# nano_neu5.net
KiCad netlist of a schematic drawn in EAGLE
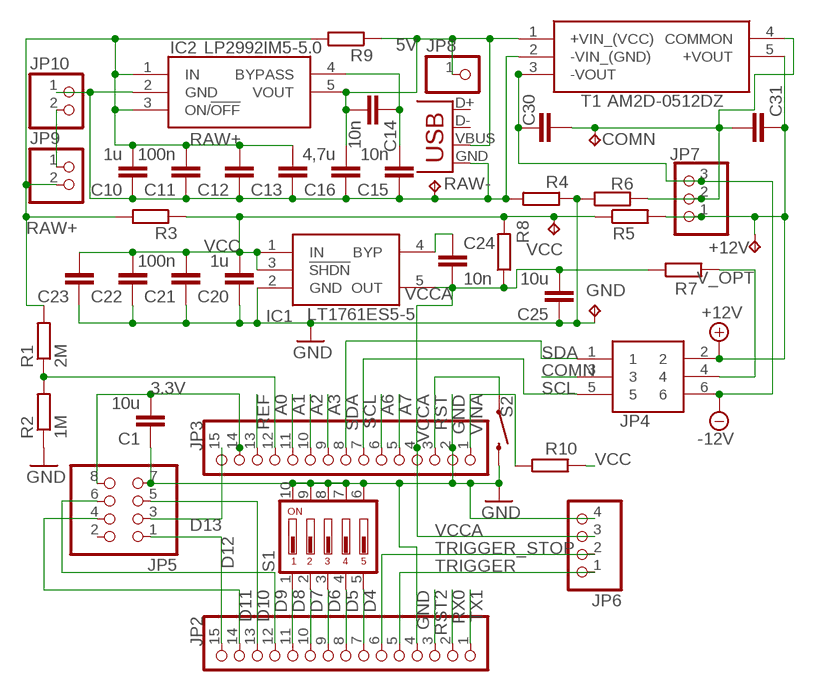
[diagram p0: schematic, sheet 1]

(export (version "E")
  (design (tool "Eeschema 10.0.6"))
  (components
    (comp (ref "+12V")
      (value "TESTPAD_TPTP09SQ")
      (footprint "eagle-import:TESTPAD_TP09SQ")
      (libsource (lib "eagle-import") (part "TESTPAD_TPTP09SQ"))
    )
    (comp (ref "C1")
      (value "10u")
      (footprint "eagle-import:RCL_C0805K")
      (libsource (lib "eagle-import") (part "RCL_C-EUC0805K"))
    )
    (comp (ref "C10")
      (value "1u")
      (footprint "eagle-import:RCL_C0805K")
      (libsource (lib "eagle-import") (part "RCL_C-EUC0805K"))
    )
    (comp (ref "C11")
      (value "100n")
      (footprint "eagle-import:RCL_C0805K")
      (libsource (lib "eagle-import") (part "RCL_C-EUC0805K"))
    )
    (comp (ref "C12")
      (value "RCL_C-EUC1206K")
      (footprint "eagle-import:RCL_C1206K")
      (libsource (lib "eagle-import") (part "RCL_C-EUC1206K"))
    )
    (comp (ref "C13")
      (value "RCL_C-EUC1206K")
      (footprint "eagle-import:RCL_C1206K")
      (libsource (lib "eagle-import") (part "RCL_C-EUC1206K"))
    )
    (comp (ref "C14")
      (value "10n")
      (footprint "eagle-import:RCL_C0805K")
      (libsource (lib "eagle-import") (part "RCL_C-EUC0805K"))
    )
    (comp (ref "C15")
      (value "10n")
      (footprint "eagle-import:RCL_C0805K")
      (libsource (lib "eagle-import") (part "RCL_C-EUC0805K"))
    )
    (comp (ref "C16")
      (value "4,7u")
      (footprint "eagle-import:RCL_C0805K")
      (libsource (lib "eagle-import") (part "RCL_C-EUC0805K"))
    )
    (comp (ref "C20")
      (value "1u")
      (footprint "eagle-import:RCL_C0805K")
      (libsource (lib "eagle-import") (part "RCL_C-EUC0805K"))
    )
    (comp (ref "C21")
      (value "100n")
      (footprint "eagle-import:RCL_C0805K")
      (libsource (lib "eagle-import") (part "RCL_C-EUC0805K"))
    )
    (comp (ref "C22")
      (value "RCL_C-EUC1206K")
      (footprint "eagle-import:RCL_C1206K")
      (libsource (lib "eagle-import") (part "RCL_C-EUC1206K"))
    )
    (comp (ref "C23")
      (value "RCL_C-EUC1206K")
      (footprint "eagle-import:RCL_C1206K")
      (libsource (lib "eagle-import") (part "RCL_C-EUC1206K"))
    )
    (comp (ref "C24")
      (value "10n")
      (footprint "eagle-import:RCL_C0805K")
      (libsource (lib "eagle-import") (part "RCL_C-EUC0805K"))
    )
    (comp (ref "C25")
      (value "10u")
      (footprint "eagle-import:RCL_C0805K")
      (libsource (lib "eagle-import") (part "RCL_C-EUC0805K"))
    )
    (comp (ref "C30")
      (value "RCL_C-EUC1206K")
      (footprint "eagle-import:RCL_C1206K")
      (libsource (lib "eagle-import") (part "RCL_C-EUC1206K"))
    )
    (comp (ref "C31")
      (value "RCL_C-EUC1206K")
      (footprint "eagle-import:RCL_C1206K")
      (libsource (lib "eagle-import") (part "RCL_C-EUC1206K"))
    )
    (comp (ref "COMN")
      (value "TESTPAD_TPTP09SQ")
      (footprint "eagle-import:TESTPAD_TP09SQ")
      (libsource (lib "eagle-import") (part "TESTPAD_TPTP09SQ"))
    )
    (comp (ref "GND")
      (value "TESTPAD_TPTP09SQ")
      (footprint "eagle-import:TESTPAD_TP09SQ")
      (libsource (lib "eagle-import") (part "TESTPAD_TPTP09SQ"))
    )
    (comp (ref "IC1")
      (value "LT1761ES5-5")
      (footprint "eagle-import:SAMACSYS_PARTS_SOT95P280X100-5N")
      (fields
        (field (name "MANUFACTURER_PART_NUMBER") "LT1761ES5-3.3#TRMPBF")
        (field (name "MOUSER_PART_NUMBER") "584-1761ES5-3.3TMPF")
      )
      (libsource (lib "eagle-import") (part "SAMACSYS_PARTS_LT1761ES5-5#TRMPBF"))
    )
    (comp (ref "IC2")
      (value "LP2992IM5-5.0")
      (footprint "eagle-import:SAMACSYS_PARTS_SOT95P280X145-5N")
      (fields
        (field (name "MANUFACTURER_PART_NUMBER") "LP2992IM5-5.0/NOPB")
        (field (name "MOUSER_PART_NUMBER") "926-2992IM5-5.0/NOPB")
      )
      (libsource (lib "eagle-import") (part "SAMACSYS_PARTS_LP2992IM5-5.0_NOPB"))
    )
    (comp (ref "JP2")
      (value "ADAFRUIT_PINHD-1X15-CB")
      (footprint "eagle-import:ADAFRUIT_1X15-CB")
      (libsource (lib "eagle-import") (part "ADAFRUIT_PINHD-1X15-CB"))
    )
    (comp (ref "JP3")
      (value "ADAFRUIT_PINHD-1X15-CB")
      (footprint "eagle-import:ADAFRUIT_1X15-CB")
      (libsource (lib "eagle-import") (part "ADAFRUIT_PINHD-1X15-CB"))
    )
    (comp (ref "JP4")
      (value "SAMACSYS_PARTS_FTSH-103-01-F-D")
      (footprint "eagle-import:SAMACSYS_PARTS_FTSH10301FD")
      (fields
        (field (name "MANUFACTURER_PART_NUMBER") "FTSH-103-01-F-D")
        (field (name "MOUSER_PART_NUMBER") "200-FTSH10301FD")
      )
      (libsource (lib "eagle-import") (part "SAMACSYS_PARTS_FTSH-103-01-F-D"))
    )
    (comp (ref "JP5")
      (value "PINHEAD_PINHD-2X4")
      (footprint "eagle-import:PINHEAD_2X04")
      (libsource (lib "eagle-import") (part "PINHEAD_PINHD-2X4"))
    )
    (comp (ref "JP6")
      (value "PINHD-1X4-CB")
      (footprint "eagle-import:ADAFRUIT_1X04-CLEANBIG")
      (libsource (lib "eagle-import") (part "PINHD-1X4-CB"))
    )
    (comp (ref "JP7")
      (value "ADAFRUIT_PINHD-1X3CB")
      (footprint "eagle-import:ADAFRUIT_1X03-CLEANBIG")
      (libsource (lib "eagle-import") (part "ADAFRUIT_PINHD-1X3CB"))
    )
    (comp (ref "JP8")
      (value "PINHEAD_PINHD-1X1")
      (footprint "eagle-import:PINHEAD_1X01")
      (libsource (lib "eagle-import") (part "PINHEAD_PINHD-1X1"))
    )
    (comp (ref "JP9")
      (value "PINHEAD_PINHD-1X2")
      (footprint "eagle-import:PINHEAD_1X02")
      (libsource (lib "eagle-import") (part "PINHEAD_PINHD-1X2"))
    )
    (comp (ref "JP10")
      (value "PINHEAD_PINHD-1X2")
      (footprint "eagle-import:PINHEAD_1X02")
      (libsource (lib "eagle-import") (part "PINHEAD_PINHD-1X2"))
    )
    (comp (ref "R1")
      (value "2M")
      (footprint "eagle-import:RCL_R0805")
      (libsource (lib "eagle-import") (part "RCL_R-EU_R0805"))
    )
    (comp (ref "R2")
      (value "1M")
      (footprint "eagle-import:RCL_R0805")
      (libsource (lib "eagle-import") (part "RCL_R-EU_R0805"))
    )
    (comp (ref "R3")
      (value "RCL_R-EU_R0805")
      (footprint "eagle-import:RCL_R0805")
      (libsource (lib "eagle-import") (part "RCL_R-EU_R0805"))
    )
    (comp (ref "R4")
      (value "RCL_R-EU_R0805")
      (footprint "eagle-import:RCL_R0805")
      (libsource (lib "eagle-import") (part "RCL_R-EU_R0805"))
    )
    (comp (ref "R5")
      (value "RCL_R-EU_R0805")
      (footprint "eagle-import:RCL_R0805")
      (libsource (lib "eagle-import") (part "RCL_R-EU_R0805"))
    )
    (comp (ref "R6")
      (value "RCL_R-EU_R0805")
      (footprint "eagle-import:RCL_R0805")
      (libsource (lib "eagle-import") (part "RCL_R-EU_R0805"))
    )
    (comp (ref "R7")
      (value "RCL_R-EU_R0805")
      (footprint "eagle-import:RCL_R0805")
      (libsource (lib "eagle-import") (part "RCL_R-EU_R0805"))
    )
    (comp (ref "R8")
      (value "RCL_R-EU_R0805")
      (footprint "eagle-import:RCL_R0805")
      (libsource (lib "eagle-import") (part "RCL_R-EU_R0805"))
    )
    (comp (ref "R9")
      (value "RCL_R-EU_R0805")
      (footprint "eagle-import:RCL_R0805")
      (libsource (lib "eagle-import") (part "RCL_R-EU_R0805"))
    )
    (comp (ref "R10")
      (value "RCL_R-EU_R0603")
      (footprint "eagle-import:RCL_R0603")
      (libsource (lib "eagle-import") (part "RCL_R-EU_R0603"))
    )
    (comp (ref "RAW-")
      (value "RAW-")
      (footprint "eagle-import:TESTPAD_TP09SQ")
      (libsource (lib "eagle-import") (part "TESTPAD_TPTP09SQ"))
    )
    (comp (ref "S1")
      (value "SWITCH-DIL_219-05")
      (footprint "eagle-import:SWITCH-DIL_CTS-219-05")
      (libsource (lib "eagle-import") (part "SWITCH-DIL_219-05"))
    )
    (comp (ref "S2")
      (value "SPARKFUN-SWITCHES_MOMENTARY-SWITCH-SPST-SMD-6.0X3.5MM")
      (footprint "eagle-import:SPARKFUN-SWITCHES_TACTILE_SWITCH_SMD_6.0X3.5MM")
      (libsource (lib "eagle-import") (part "SPARKFUN-SWITCHES_MOMENTARY-SWITCH-SPST-SMD-6.0X3.5MM"))
    )
    (comp (ref "T1")
      (value "AM2D-0512DZ")
      (footprint "eagle-import:SAMACSYS_PARTS_TMA-0512D")
      (fields
        (field (name "MANUFACTURER_PART_NUMBER") "TMA 0512D")
        (field (name "MOUSER_PART_NUMBER") "495-TMA-0512D")
      )
      (libsource (lib "eagle-import") (part "SAMACSYS_PARTS_TMA_0512D"))
    )
    (comp (ref "VCC")
      (value "TESTPAD_TPTP09SQ")
      (footprint "eagle-import:TESTPAD_TP09SQ")
      (libsource (lib "eagle-import") (part "TESTPAD_TPTP09SQ"))
    )
    (comp (ref "X1")
      (value "CON-USB_USB-MB-S")
      (footprint "eagle-import:CON-USB_USB-MB-S")
      (libsource (lib "eagle-import") (part "CON-USB_USB-MB-S"))
    )
  )
  (nets
    (net (code "1") (name "+12V") (class "Default")
      (node (ref "+12V") (pin "TP") (pinfunction "TP_TP") (pintype "input"))
      (node (ref "C31") (pin "1") (pinfunction "1_1") (pintype "passive"))
      (node (ref "JP4") (pin "2") (pinfunction "2_2") (pintype "bidirectional"))
      (node (ref "JP7") (pin "1") (pinfunction "1_1") (pintype "passive"))
      (node (ref "R5") (pin "2") (pinfunction "2_2") (pintype "passive"))
      (node (ref "T1") (pin "5") (pinfunction "+VOUT_5") (pintype "bidirectional"))
    )
    (net (code "2") (name "-12V") (class "Default")
      (node (ref "C30") (pin "1") (pinfunction "1_1") (pintype "passive"))
      (node (ref "JP4") (pin "6") (pinfunction "6_6") (pintype "bidirectional"))
      (node (ref "JP7") (pin "3") (pinfunction "3_3") (pintype "passive"))
      (node (ref "T1") (pin "3") (pinfunction "-VOUT_3") (pintype "bidirectional"))
    )
    (net (code "3") (name "/3.3V") (class "Default")
      (node (ref "C1") (pin "2") (pinfunction "2_2") (pintype "passive"))
      (node (ref "JP3") (pin "14") (pinfunction "14_14") (pintype "passive"))
      (node (ref "JP5") (pin "8") (pinfunction "8_8") (pintype "passive"))
    )
    (net (code "4") (name "/5V") (class "Default")
      (node (ref "C14") (pin "2") (pinfunction "2_2") (pintype "passive"))
      (node (ref "C16") (pin "2") (pinfunction "2_2") (pintype "passive"))
      (node (ref "IC2") (pin "5") (pinfunction "VOUT_5") (pintype "output"))
      (node (ref "JP8") (pin "1") (pinfunction "1_1") (pintype "passive"))
      (node (ref "R9") (pin "1") (pinfunction "1_1") (pintype "passive"))
      (node (ref "T1") (pin "1") (pinfunction "+VIN_(VCC)_1") (pintype "bidirectional"))
      (node (ref "X1") (pin "VBUS") (pinfunction "VBUS_VBUS") (pintype "bidirectional"))
    )
    (net (code "5") (name "/A0") (class "Default")
      (node (ref "JP3") (pin "12") (pinfunction "12_12") (pintype "passive"))
      (node (ref "R1") (pin "1") (pinfunction "1_1") (pintype "passive"))
      (node (ref "R2") (pin "2") (pinfunction "2_2") (pintype "passive"))
    )
    (net (code "6") (name "/A1") (class "Default")
      (node (ref "JP3") (pin "11") (pinfunction "11_11") (pintype "passive"))
    )
    (net (code "7") (name "/A2") (class "Default")
      (node (ref "JP3") (pin "10") (pinfunction "10_10") (pintype "passive"))
    )
    (net (code "8") (name "/A3") (class "Default")
      (node (ref "JP3") (pin "9") (pinfunction "9_9") (pintype "passive"))
    )
    (net (code "9") (name "/A6") (class "Default")
      (node (ref "JP3") (pin "6") (pinfunction "6_6") (pintype "passive"))
    )
    (net (code "10") (name "/A7") (class "Default")
      (node (ref "JP3") (pin "5") (pinfunction "5_5") (pintype "passive"))
    )
    (net (code "11") (name "/COMN") (class "Default")
      (node (ref "C30") (pin "2") (pinfunction "2_2") (pintype "passive"))
      (node (ref "C31") (pin "2") (pinfunction "2_2") (pintype "passive"))
      (node (ref "COMN") (pin "TP") (pinfunction "TP_TP") (pintype "input"))
      (node (ref "JP4") (pin "3") (pinfunction "3_3") (pintype "bidirectional"))
      (node (ref "JP7") (pin "2") (pinfunction "2_2") (pintype "passive"))
      (node (ref "R6") (pin "2") (pinfunction "2_2") (pintype "passive"))
      (node (ref "T1") (pin "4") (pinfunction "COMMON_4") (pintype "bidirectional"))
    )
    (net (code "12") (name "/D4") (class "Default")
      (node (ref "JP2") (pin "7") (pinfunction "7_7") (pintype "passive"))
      (node (ref "S1") (pin "5") (pinfunction "5_5") (pintype "passive"))
    )
    (net (code "13") (name "/D5") (class "Default")
      (node (ref "JP2") (pin "8") (pinfunction "8_8") (pintype "passive"))
      (node (ref "S1") (pin "4") (pinfunction "4_4") (pintype "passive"))
    )
    (net (code "14") (name "/D6") (class "Default")
      (node (ref "JP2") (pin "9") (pinfunction "9_9") (pintype "passive"))
      (node (ref "S1") (pin "3") (pinfunction "3_3") (pintype "passive"))
    )
    (net (code "15") (name "/D7") (class "Default")
      (node (ref "JP2") (pin "10") (pinfunction "10_10") (pintype "passive"))
      (node (ref "S1") (pin "2") (pinfunction "2_2") (pintype "passive"))
    )
    (net (code "16") (name "/D8") (class "Default")
      (node (ref "JP2") (pin "11") (pinfunction "11_11") (pintype "passive"))
      (node (ref "S1") (pin "1") (pinfunction "1_1") (pintype "passive"))
    )
    (net (code "17") (name "/D9") (class "Default")
      (node (ref "JP2") (pin "12") (pinfunction "12_12") (pintype "passive"))
      (node (ref "JP5") (pin "6") (pinfunction "6_6") (pintype "passive"))
    )
    (net (code "18") (name "/D10") (class "Default")
      (node (ref "JP2") (pin "13") (pinfunction "13_13") (pintype "passive"))
      (node (ref "JP5") (pin "5") (pinfunction "5_5") (pintype "passive"))
    )
    (net (code "19") (name "/D11") (class "Default")
      (node (ref "JP2") (pin "14") (pinfunction "14_14") (pintype "passive"))
      (node (ref "JP5") (pin "4") (pinfunction "4_4") (pintype "passive"))
    )
    (net (code "20") (name "/D12") (class "Default")
      (node (ref "JP2") (pin "15") (pinfunction "15_15") (pintype "passive"))
      (node (ref "JP5") (pin "1") (pinfunction "1_1") (pintype "passive"))
    )
    (net (code "21") (name "/D13") (class "Default")
      (node (ref "JP3") (pin "15") (pinfunction "15_15") (pintype "passive"))
      (node (ref "JP5") (pin "3") (pinfunction "3_3") (pintype "passive"))
    )
    (net (code "22") (name "/RAW+") (class "Default")
      (node (ref "C10") (pin "2") (pinfunction "2_2") (pintype "passive"))
      (node (ref "C11") (pin "2") (pinfunction "2_2") (pintype "passive"))
      (node (ref "C12") (pin "2") (pinfunction "2_2") (pintype "passive"))
      (node (ref "C13") (pin "2") (pinfunction "2_2") (pintype "passive"))
      (node (ref "IC2") (pin "1") (pinfunction "IN_1") (pintype "input"))
      (node (ref "IC2") (pin "3") (pinfunction "ON/~{OFF}_3") (pintype "bidirectional"))
      (node (ref "JP9") (pin "2") (pinfunction "2_2") (pintype "passive"))
      (node (ref "R1") (pin "2") (pinfunction "2_2") (pintype "passive"))
      (node (ref "R3") (pin "2") (pinfunction "2_2") (pintype "passive"))
      (node (ref "R9") (pin "2") (pinfunction "2_2") (pintype "passive"))
    )
    (net (code "23") (name "/REF") (class "Default")
      (node (ref "JP3") (pin "13") (pinfunction "13_13") (pintype "passive"))
    )
    (net (code "24") (name "/RST") (class "Default")
      (node (ref "JP3") (pin "3") (pinfunction "3_3") (pintype "passive"))
      (node (ref "S2") (pin "1") (pinfunction "1_1") (pintype "passive"))
    )
    (net (code "25") (name "/RST2") (class "Default")
      (node (ref "JP2") (pin "3") (pinfunction "3_3") (pintype "passive"))
    )
    (net (code "26") (name "/RX0") (class "Default")
      (node (ref "JP2") (pin "2") (pinfunction "2_2") (pintype "passive"))
    )
    (net (code "27") (name "/SCL") (class "Default")
      (node (ref "JP3") (pin "7") (pinfunction "7_7") (pintype "passive"))
      (node (ref "JP4") (pin "5") (pinfunction "5_5") (pintype "bidirectional"))
    )
    (net (code "28") (name "/SDA") (class "Default")
      (node (ref "JP3") (pin "8") (pinfunction "8_8") (pintype "passive"))
      (node (ref "JP4") (pin "1") (pinfunction "1_1") (pintype "bidirectional"))
    )
    (net (code "29") (name "/TRIGGER") (class "Default")
      (node (ref "JP2") (pin "5") (pinfunction "5_5") (pintype "passive"))
      (node (ref "JP6") (pin "1") (pinfunction "1_1") (pintype "passive"))
    )
    (net (code "30") (name "/TRIGGER_STOP") (class "Default")
      (node (ref "JP2") (pin "6") (pinfunction "6_6") (pintype "passive"))
      (node (ref "JP6") (pin "2") (pinfunction "2_2") (pintype "passive"))
    )
    (net (code "31") (name "/TX1") (class "Default")
      (node (ref "JP2") (pin "1") (pinfunction "1_1") (pintype "passive"))
    )
    (net (code "32") (name "/VCC") (class "Default")
      (node (ref "C20") (pin "2") (pinfunction "2_2") (pintype "passive"))
      (node (ref "C21") (pin "2") (pinfunction "2_2") (pintype "passive"))
      (node (ref "C22") (pin "2") (pinfunction "2_2") (pintype "passive"))
      (node (ref "C23") (pin "2") (pinfunction "2_2") (pintype "passive"))
      (node (ref "IC1") (pin "1") (pinfunction "IN_1") (pintype "bidirectional"))
      (node (ref "IC1") (pin "3") (pinfunction "~{SHDN}_3") (pintype "bidirectional"))
      (node (ref "R10") (pin "1") (pinfunction "1_1") (pintype "passive"))
      (node (ref "R3") (pin "1") (pinfunction "1_1") (pintype "passive"))
      (node (ref "R5") (pin "1") (pinfunction "1_1") (pintype "passive"))
      (node (ref "R8") (pin "2") (pinfunction "2_2") (pintype "passive"))
      (node (ref "VCC") (pin "TP") (pinfunction "TP_TP") (pintype "input"))
    )
    (net (code "33") (name "/VCCA") (class "Default")
      (node (ref "C24") (pin "2") (pinfunction "2_2") (pintype "passive"))
      (node (ref "C25") (pin "2") (pinfunction "2_2") (pintype "passive"))
      (node (ref "IC1") (pin "5") (pinfunction "OUT_5") (pintype "bidirectional"))
      (node (ref "JP3") (pin "4") (pinfunction "4_4") (pintype "passive"))
      (node (ref "JP6") (pin "3") (pinfunction "3_3") (pintype "passive"))
      (node (ref "R7") (pin "1") (pinfunction "1_1") (pintype "passive"))
      (node (ref "R8") (pin "1") (pinfunction "1_1") (pintype "passive"))
    )
    (net (code "34") (name "/VINA") (class "Default")
      (node (ref "JP3") (pin "1") (pinfunction "1_1") (pintype "passive"))
      (node (ref "R10") (pin "2") (pinfunction "2_2") (pintype "passive"))
    )
    (net (code "35") (name "/V_OPT") (class "Default")
      (node (ref "JP4") (pin "4") (pinfunction "4_4") (pintype "bidirectional"))
      (node (ref "R7") (pin "2") (pinfunction "2_2") (pintype "passive"))
    )
    (net (code "36") (name "GND") (class "Default")
      (node (ref "C1") (pin "1") (pinfunction "1_1") (pintype "passive"))
      (node (ref "C20") (pin "1") (pinfunction "1_1") (pintype "passive"))
      (node (ref "C21") (pin "1") (pinfunction "1_1") (pintype "passive"))
      (node (ref "C22") (pin "1") (pinfunction "1_1") (pintype "passive"))
      (node (ref "C23") (pin "1") (pinfunction "1_1") (pintype "passive"))
      (node (ref "C25") (pin "1") (pinfunction "1_1") (pintype "passive"))
      (node (ref "GND") (pin "TP") (pinfunction "TP_TP") (pintype "input"))
      (node (ref "IC1") (pin "2") (pinfunction "GND_2") (pintype "bidirectional"))
      (node (ref "JP2") (pin "4") (pinfunction "4_4") (pintype "passive"))
      (node (ref "JP3") (pin "2") (pinfunction "2_2") (pintype "passive"))
      (node (ref "JP5") (pin "7") (pinfunction "7_7") (pintype "passive"))
      (node (ref "JP6") (pin "4") (pinfunction "4_4") (pintype "passive"))
      (node (ref "R2") (pin "1") (pinfunction "1_1") (pintype "passive"))
      (node (ref "R4") (pin "1") (pinfunction "1_1") (pintype "passive"))
      (node (ref "R6") (pin "1") (pinfunction "1_1") (pintype "passive"))
      (node (ref "S1") (pin "10") (pinfunction "10_10") (pintype "passive"))
      (node (ref "S1") (pin "6") (pinfunction "6_6") (pintype "passive"))
      (node (ref "S1") (pin "7") (pinfunction "7_7") (pintype "passive"))
      (node (ref "S1") (pin "8") (pinfunction "8_8") (pintype "passive"))
      (node (ref "S1") (pin "9") (pinfunction "9_9") (pintype "passive"))
      (node (ref "S2") (pin "2") (pinfunction "2_2") (pintype "passive"))
    )
    (net (code "37") (name "Net-(IC1-BYP)") (class "Default")
      (node (ref "C24") (pin "1") (pinfunction "1_1") (pintype "passive"))
      (node (ref "IC1") (pin "4") (pinfunction "BYP_4") (pintype "bidirectional"))
    )
    (net (code "38") (name "Net-(IC2-BYPASS)") (class "Default")
      (node (ref "C14") (pin "1") (pinfunction "1_1") (pintype "passive"))
      (node (ref "C15") (pin "2") (pinfunction "2_2") (pintype "passive"))
      (node (ref "IC2") (pin "4") (pinfunction "BYPASS_4") (pintype "bidirectional"))
    )
    (net (code "39") (name "Net-(IC2-GND)") (class "Default")
      (node (ref "C10") (pin "1") (pinfunction "1_1") (pintype "passive"))
      (node (ref "C11") (pin "1") (pinfunction "1_1") (pintype "passive"))
      (node (ref "C12") (pin "1") (pinfunction "1_1") (pintype "passive"))
      (node (ref "C13") (pin "1") (pinfunction "1_1") (pintype "passive"))
      (node (ref "C15") (pin "1") (pinfunction "1_1") (pintype "passive"))
      (node (ref "C16") (pin "1") (pinfunction "1_1") (pintype "passive"))
      (node (ref "IC2") (pin "2") (pinfunction "GND_2") (pintype "power_in"))
      (node (ref "JP10") (pin "1") (pinfunction "1_1") (pintype "passive"))
      (node (ref "R4") (pin "2") (pinfunction "2_2") (pintype "passive"))
      (node (ref "RAW-") (pin "TP") (pinfunction "TP_TP") (pintype "input"))
      (node (ref "T1") (pin "2") (pinfunction "-VIN_(GND)_2") (pintype "bidirectional"))
      (node (ref "X1") (pin "GND") (pinfunction "GND_GND") (pintype "bidirectional"))
    )
    (net (code "40") (name "Net-(JP10-Pad2)") (class "Default")
      (node (ref "JP10") (pin "2") (pinfunction "2_2") (pintype "passive"))
      (node (ref "JP9") (pin "1") (pinfunction "1_1") (pintype "passive"))
    )
    (net (code "41") (name "unconnected-(JP5-Pad2)") (class "Default")
      (node (ref "JP5") (pin "2") (pinfunction "2_2") (pintype "passive"))
    )
    (net (code "42") (name "unconnected-(X1-PadD+)") (class "Default")
      (node (ref "X1") (pin "D+") (pinfunction "D+_D+") (pintype "bidirectional"))
    )
    (net (code "43") (name "unconnected-(X1-PadD-)") (class "Default")
      (node (ref "X1") (pin "D-") (pinfunction "D-_D-") (pintype "bidirectional"))
    )
  )
)
